# controller_2.net
KiCad netlist of a schematic drawn in EasyEDA Pro
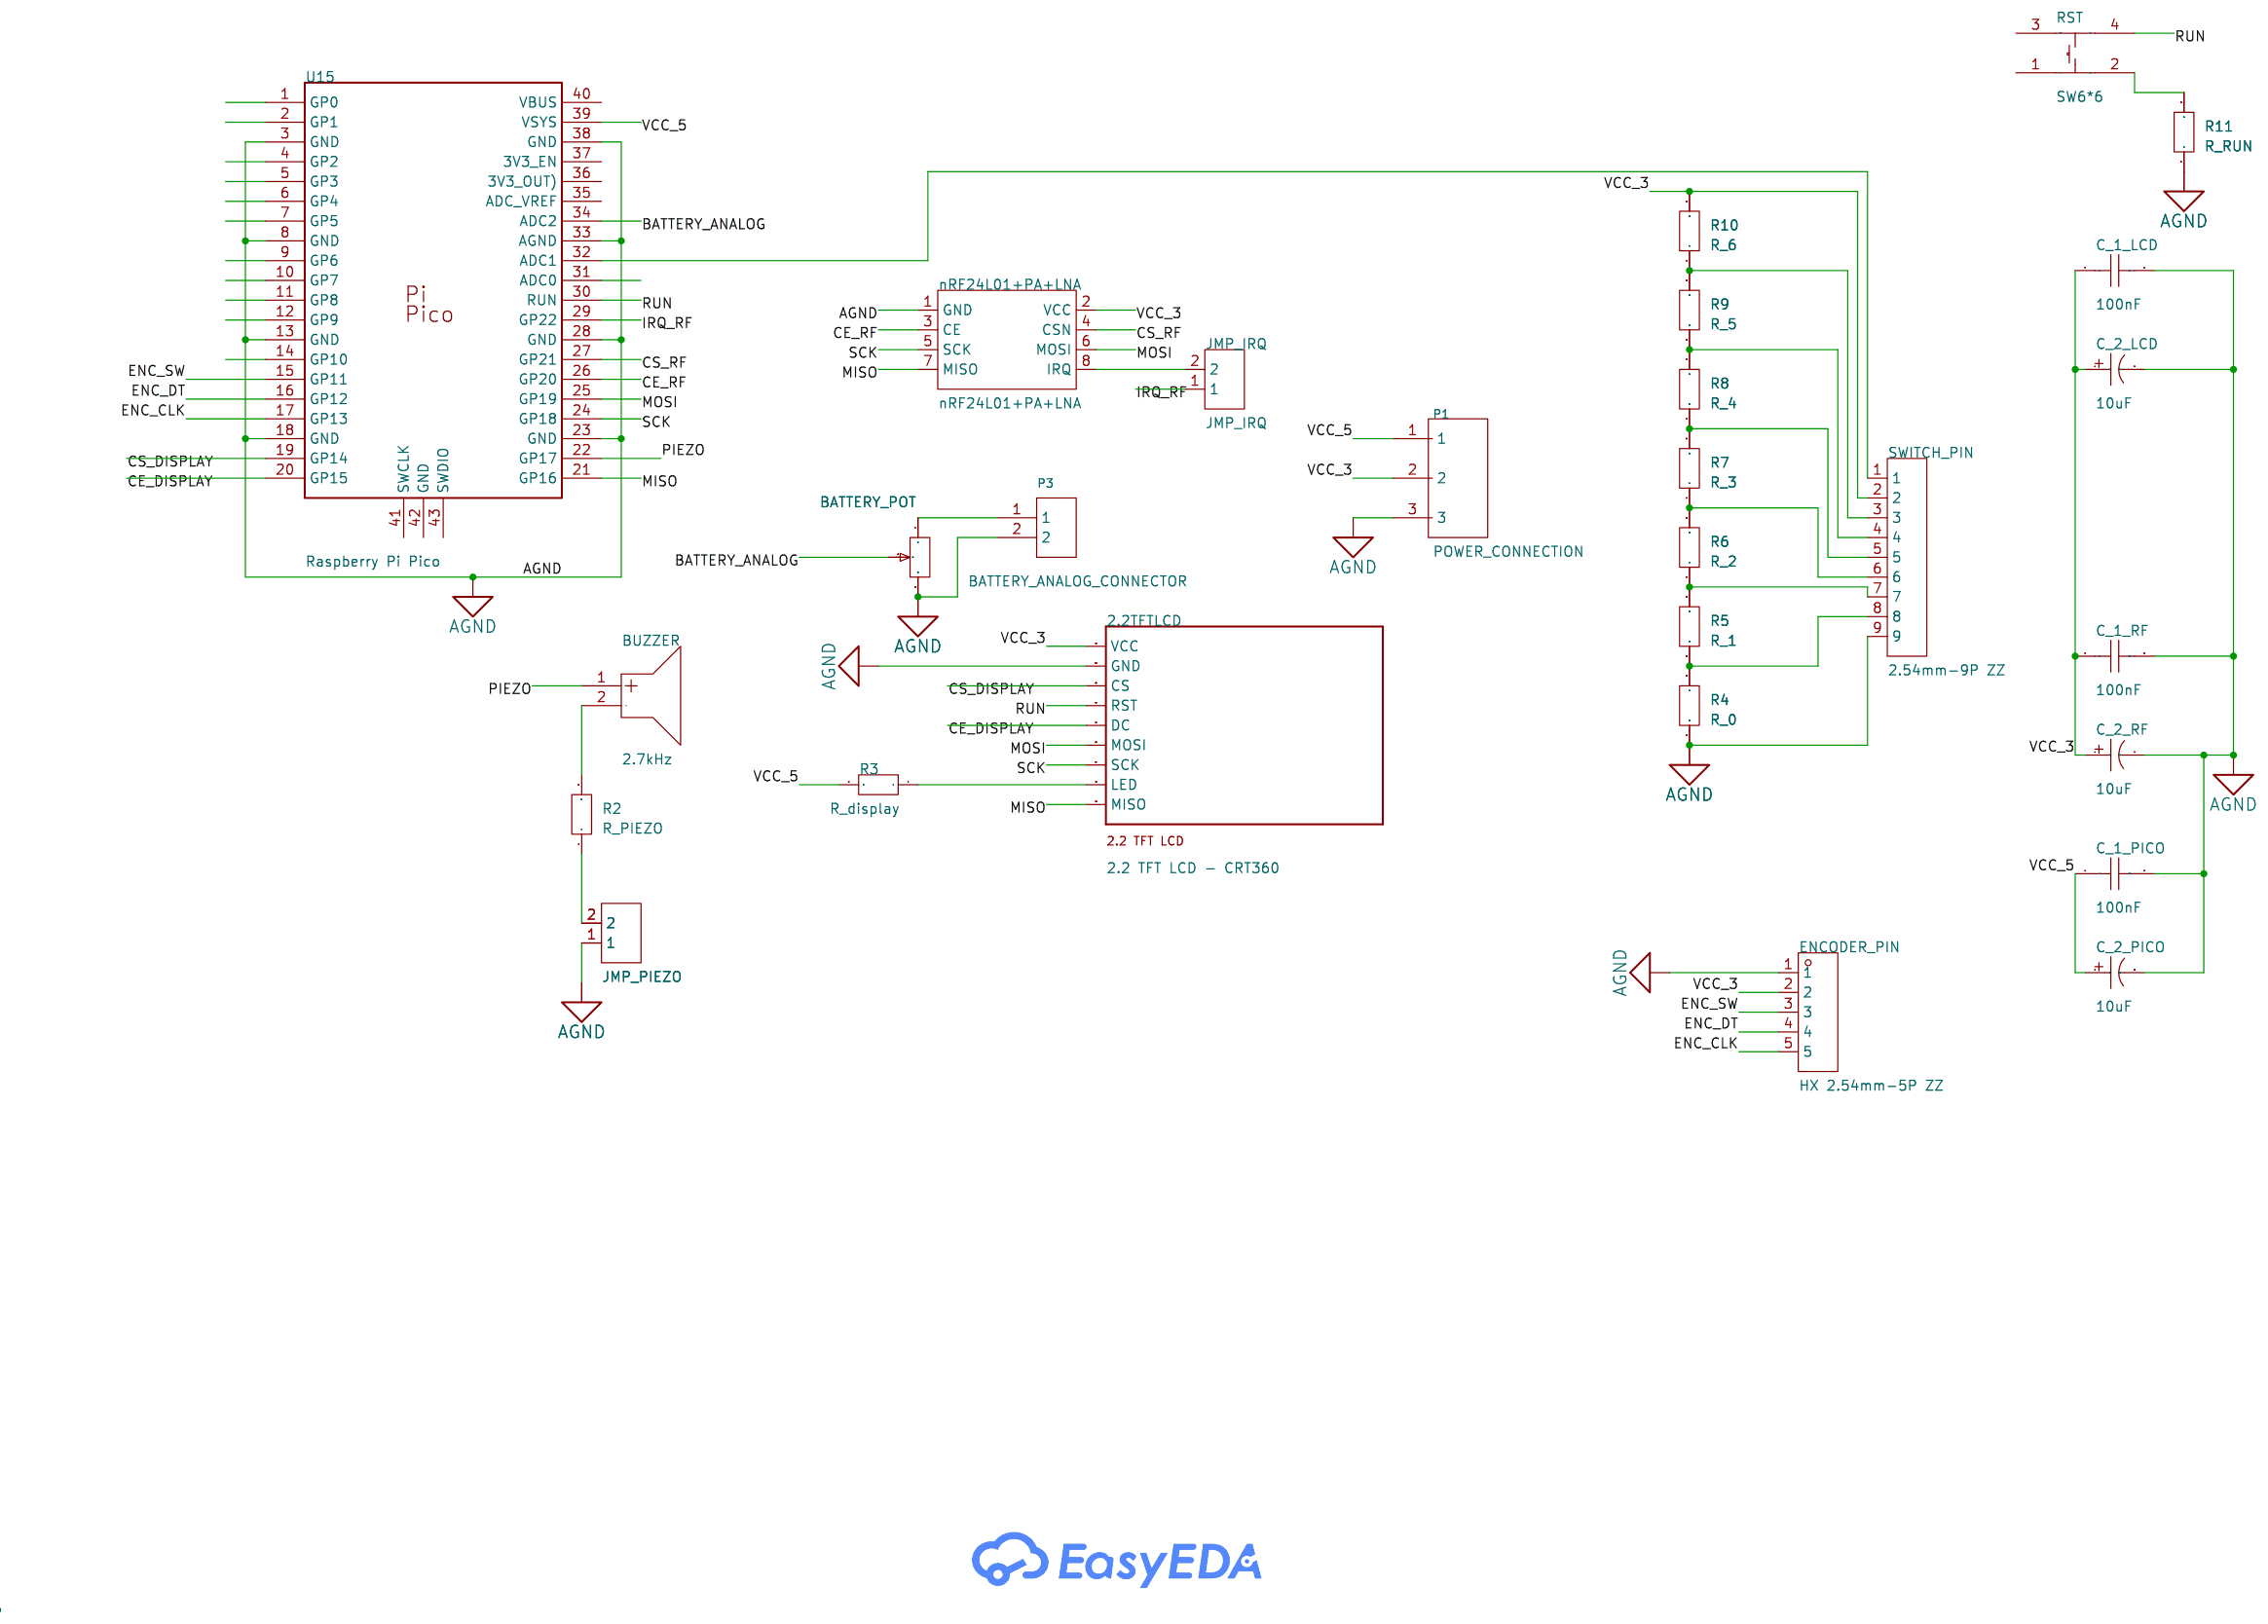
[diagram p0: schematic sheet]

(export (version "E")
  (design (tool "Eeschema 10.0.6"))
  (components
    (comp (ref "2.2TFTLCD")
      (value "2.2 TFT LCD - CRT360")
      (libsource (lib "easyedapro") (part "2.2 TFT LCD - CRT360"))
    )
    (comp (ref "BUZZER")
      (value "2.7kHz")
      (footprint "easyedapro:BUZ-TH_BD9.0-P5.00-D0.6-FD")
      (fields (field (name "Manufacturer Part") "FMB09A03-3V") (field (name "Manufacturer") "FUET(福声科技)"))
      (libsource (lib "easyedapro") (part "FMB09A03-3V_C417385"))
    )
    (comp (ref "C_1_LCD")
      (value "100nF")
      (footprint "easyedapro:CAP-TH_L5.8-W3.6-P5.0-D0.6")
      (fields (field (name "Manufacturer Part") "178MU0002") (field (name "Manufacturer") "KNSCHA(科尼盛)"))
      (libsource (lib "easyedapro") (part "178MU0002"))
    )
    (comp (ref "C_1_PICO")
      (value "100nF")
      (footprint "easyedapro:CAP-TH_L5.8-W3.6-P5.0-D0.6")
      (fields (field (name "Manufacturer Part") "178MU0002") (field (name "Manufacturer") "KNSCHA(科尼盛)"))
      (libsource (lib "easyedapro") (part "178MU0002"))
    )
    (comp (ref "C_1_RF")
      (value "100nF")
      (footprint "easyedapro:CAP-TH_L5.8-W3.6-P5.0-D0.6")
      (fields (field (name "Manufacturer Part") "178MU0002") (field (name "Manufacturer") "KNSCHA(科尼盛)"))
      (libsource (lib "easyedapro") (part "178MU0002"))
    )
    (comp (ref "C_2_LCD")
      (value "10uF")
      (footprint "easyedapro:CAP-TH_BD8.0-P3.50-D0.6-FD")
      (fields
        (field (name "Manufacturer Part") "35ZLH220MEFC8X11.5")
        (field (name "Manufacturer") "Rubycon(红宝石)")
      )
      (libsource (lib "easyedapro") (part "35ZLH220MEFC8X11.5"))
    )
    (comp (ref "C_2_PICO")
      (value "10uF")
      (footprint "easyedapro:CAP-TH_BD8.0-P3.50-D0.6-FD")
      (fields
        (field (name "Manufacturer Part") "35ZLH220MEFC8X11.5")
        (field (name "Manufacturer") "Rubycon(红宝石)")
      )
      (libsource (lib "easyedapro") (part "35ZLH220MEFC8X11.5"))
    )
    (comp (ref "C_2_RF")
      (value "10uF")
      (footprint "easyedapro:CAP-TH_BD8.0-P3.50-D0.6-FD")
      (fields
        (field (name "Manufacturer Part") "35ZLH220MEFC8X11.5")
        (field (name "Manufacturer") "Rubycon(红宝石)")
      )
      (libsource (lib "easyedapro") (part "35ZLH220MEFC8X11.5"))
    )
    (comp (ref "ENCODER_PIN")
      (value "HX 2.54mm-5P ZZ")
      (footprint "easyedapro:CONN-TH_5P-P2.50_HX-2.54MM-5P-ZZ")
      (fields (field (name "Manufacturer") "hanxia(韩下)"))
      (libsource (lib "easyedapro") (part "HX 2.54MM-5P ZZ"))
    )
    (comp (ref "H2")
      (value "JMP_PIEZO")
      (footprint "easyedapro:HDR-TH_2P-P2.54-V-M")
      (fields (field (name "Manufacturer Part") "PZ254V-11-02P") (field (name "Manufacturer") "XFCN(兴飞)"))
      (libsource (lib "easyedapro") (part "PZ254V-11-02P"))
    )
    (comp (ref "JMP_IRQ")
      (value "JMP_IRQ")
      (footprint "easyedapro:HDR-TH_2P-P2.54-V-M")
      (fields (field (name "Manufacturer Part") "PZ254V-11-02P") (field (name "Manufacturer") "XFCN(兴飞)"))
      (libsource (lib "easyedapro") (part "PZ254V-11-02P"))
    )
    (comp (ref "nRF24L01+PA+LNA")
      (value "nRF24L01+PA+LNA")
      (footprint "easyedapro:COMM-TH_L41.0-W15.5-P2.54_NRF24L01")
      (libsource (lib "easyedapro") (part "NRF24L01+PA+LNA"))
    )
    (comp (ref "P1")
      (value "POWER_CONNECTION")
      (footprint "easyedapro:CONN-TH_3P-P5.00_WJ126V-5.0-3P")
      (fields
        (field (name "Manufacturer Part") "WJ126V-5.0-3P")
        (field (name "Manufacturer") "KANGNEX(康奈克斯电气)")
      )
      (libsource (lib "easyedapro") (part "WJ126V-5.0-3P"))
    )
    (comp (ref "P3")
      (value "BATTERY_ANALOG_CONNECTOR")
      (footprint "easyedapro:CONN-TH_2P-P5.00_WJ301V-5.00-2P")
      (fields
        (field (name "Manufacturer Part") "WJ301V-5.0-2P")
        (field (name "Manufacturer") "KANGNEX(康奈克斯电气)")
      )
      (libsource (lib "easyedapro") (part "WJ301V-5.0-2P"))
    )
    (comp (ref "R1")
      (value "20kΩ")
      (footprint "easyedapro:RES-ADJ-TH_3296X")
      (fields (field (name "Manufacturer Part") "3296X-203") (field (name "Manufacturer") "BAOTER(宝特)"))
      (libsource (lib "easyedapro") (part "3296X-203"))
    )
    (comp (ref "R2")
      (value "10kΩ")
      (footprint "easyedapro:RES-TH_BD5.0-L15.5-P19.50-D0.7")
      (fields
        (field (name "Manufacturer Part") "MF02SFF1002A10")
        (field (name "Manufacturer") "UNI-ROYAL(厚声)")
      )
      (libsource (lib "easyedapro") (part "MF02SFF1002A10"))
    )
    (comp (ref "R3")
      (value "10kΩ")
      (footprint "easyedapro:RES-TH_BD5.0-L15.5-P19.50-D0.7")
      (fields
        (field (name "Manufacturer Part") "MF02SFF1002A10")
        (field (name "Manufacturer") "UNI-ROYAL(厚声)")
      )
      (libsource (lib "easyedapro") (part "MF02SFF1002A10"))
    )
    (comp (ref "R4")
      (value "10kΩ")
      (footprint "easyedapro:RES-TH_BD5.0-L15.5-P19.50-D0.7")
      (fields
        (field (name "Manufacturer Part") "MF02SFF1002A10")
        (field (name "Manufacturer") "UNI-ROYAL(厚声)")
      )
      (libsource (lib "easyedapro") (part "MF02SFF1002A10"))
    )
    (comp (ref "R5")
      (value "10kΩ")
      (footprint "easyedapro:RES-TH_BD5.0-L15.5-P19.50-D0.7")
      (fields
        (field (name "Manufacturer Part") "MF02SFF1002A10")
        (field (name "Manufacturer") "UNI-ROYAL(厚声)")
      )
      (libsource (lib "easyedapro") (part "MF02SFF1002A10"))
    )
    (comp (ref "R6")
      (value "10kΩ")
      (footprint "easyedapro:RES-TH_BD5.0-L15.5-P19.50-D0.7")
      (fields
        (field (name "Manufacturer Part") "MF02SFF1002A10")
        (field (name "Manufacturer") "UNI-ROYAL(厚声)")
      )
      (libsource (lib "easyedapro") (part "MF02SFF1002A10"))
    )
    (comp (ref "R7")
      (value "10kΩ")
      (footprint "easyedapro:RES-TH_BD5.0-L15.5-P19.50-D0.7")
      (fields
        (field (name "Manufacturer Part") "MF02SFF1002A10")
        (field (name "Manufacturer") "UNI-ROYAL(厚声)")
      )
      (libsource (lib "easyedapro") (part "MF02SFF1002A10"))
    )
    (comp (ref "R8")
      (value "10kΩ")
      (footprint "easyedapro:RES-TH_BD5.0-L15.5-P19.50-D0.7")
      (fields
        (field (name "Manufacturer Part") "MF02SFF1002A10")
        (field (name "Manufacturer") "UNI-ROYAL(厚声)")
      )
      (libsource (lib "easyedapro") (part "MF02SFF1002A10"))
    )
    (comp (ref "R9")
      (value "10kΩ")
      (footprint "easyedapro:RES-TH_BD5.0-L15.5-P19.50-D0.7")
      (fields
        (field (name "Manufacturer Part") "MF02SFF1002A10")
        (field (name "Manufacturer") "UNI-ROYAL(厚声)")
      )
      (libsource (lib "easyedapro") (part "MF02SFF1002A10"))
    )
    (comp (ref "R10")
      (value "10kΩ")
      (footprint "easyedapro:RES-TH_BD5.0-L15.5-P19.50-D0.7")
      (fields
        (field (name "Manufacturer Part") "MF02SFF1002A10")
        (field (name "Manufacturer") "UNI-ROYAL(厚声)")
      )
      (libsource (lib "easyedapro") (part "MF02SFF1002A10"))
    )
    (comp (ref "R11")
      (value "10kΩ")
      (footprint "easyedapro:RES-TH_BD5.0-L15.5-P19.50-D0.7")
      (fields
        (field (name "Manufacturer Part") "MF02SFF1002A10")
        (field (name "Manufacturer") "UNI-ROYAL(厚声)")
      )
      (libsource (lib "easyedapro") (part "MF02SFF1002A10"))
    )
    (comp (ref "RST")
      (value "SW6*6")
      (footprint "easyedapro:KEY-TH_4P-L6.0-W6.0-P4.5-LS6.5-TL")
      (libsource (lib "easyedapro") (part "SW6*6"))
    )
    (comp (ref "SWITCH_PIN")
      (value "2.54mm-9P ZZ")
      (footprint "easyedapro:CONN-TH_9P-P2.50_HX-2.54MM-9P-ZZ")
      (fields (field (name "Manufacturer") "SHOU HAN(首韩)"))
      (libsource (lib "easyedapro") (part "2.54MM-9P ZZ"))
    )
    (comp (ref "U15")
      (value "Raspberry Pi Pico")
      (fields (field (name "Manufacturer Part") "Pi Pico") (field (name "Manufacturer") "Raspberry Pi"))
      (libsource (lib "easyedapro") (part "Raspberry Pi Pico"))
    )
  )
  (nets
    (net (code "1") (name "/BATTERY_ANALOG") (class "Default")
      (node (ref "R1") (pin "2") (pinfunction "2_2") (pintype "input"))
      (node (ref "U15") (pin "34") (pinfunction "ADC2_34") (pintype "unspecified"))
    )
    (net (code "2") (name "/CE_DISPLAY") (class "Default")
      (node (ref "2.2TFTLCD") (pin "DC") (pinfunction "DC_DC") (pintype "unspecified"))
      (node (ref "U15") (pin "20") (pinfunction "GP15_20") (pintype "unspecified"))
    )
    (net (code "3") (name "/CE_RF") (class "Default")
      (node (ref "U15") (pin "26") (pinfunction "GP20_26") (pintype "unspecified"))
      (node (ref "nRF24L01+PA+LNA") (pin "3") (pinfunction "CE_3") (pintype "unspecified"))
    )
    (net (code "4") (name "/CS_DISPLAY") (class "Default")
      (node (ref "2.2TFTLCD") (pin "CS") (pinfunction "CS_CS") (pintype "unspecified"))
      (node (ref "U15") (pin "19") (pinfunction "GP14_19") (pintype "unspecified"))
    )
    (net (code "5") (name "/CS_RF") (class "Default")
      (node (ref "U15") (pin "27") (pinfunction "GP21_27") (pintype "unspecified"))
      (node (ref "nRF24L01+PA+LNA") (pin "4") (pinfunction "CSN_4") (pintype "unspecified"))
    )
    (net (code "6") (name "/ENC_CLK") (class "Default")
      (node (ref "ENCODER_PIN") (pin "5") (pinfunction "5_5") (pintype "unspecified"))
      (node (ref "U15") (pin "17") (pinfunction "GP13_17") (pintype "unspecified"))
    )
    (net (code "7") (name "/ENC_DT") (class "Default")
      (node (ref "ENCODER_PIN") (pin "4") (pinfunction "4_4") (pintype "unspecified"))
      (node (ref "U15") (pin "16") (pinfunction "GP12_16") (pintype "unspecified"))
    )
    (net (code "8") (name "/ENC_SW") (class "Default")
      (node (ref "ENCODER_PIN") (pin "3") (pinfunction "3_3") (pintype "unspecified"))
      (node (ref "U15") (pin "15") (pinfunction "GP11_15") (pintype "unspecified"))
    )
    (net (code "9") (name "/IRQ_RF") (class "Default")
      (node (ref "JMP_IRQ") (pin "1") (pinfunction "1_1") (pintype "unspecified"))
      (node (ref "U15") (pin "29") (pinfunction "GP22_29") (pintype "unspecified"))
    )
    (net (code "10") (name "/MISO") (class "Default")
      (node (ref "2.2TFTLCD") (pin "MISO") (pinfunction "MISO_MISO") (pintype "unspecified"))
      (node (ref "U15") (pin "21") (pinfunction "GP16_21") (pintype "unspecified"))
      (node (ref "nRF24L01+PA+LNA") (pin "7") (pinfunction "MISO_7") (pintype "unspecified"))
    )
    (net (code "11") (name "/MOSI") (class "Default")
      (node (ref "2.2TFTLCD") (pin "MOSI") (pinfunction "MOSI_MOSI") (pintype "unspecified"))
      (node (ref "U15") (pin "25") (pinfunction "GP19_25") (pintype "unspecified"))
      (node (ref "nRF24L01+PA+LNA") (pin "6") (pinfunction "MOSI_6") (pintype "unspecified"))
    )
    (net (code "12") (name "/PIEZO") (class "Default")
      (node (ref "BUZZER") (pin "1") (pinfunction "+_1") (pintype "unspecified"))
      (node (ref "U15") (pin "22") (pinfunction "GP17_22") (pintype "unspecified"))
    )
    (net (code "13") (name "/RUN") (class "Default")
      (node (ref "2.2TFTLCD") (pin "RST") (pinfunction "RST_RST") (pintype "unspecified"))
      (node (ref "RST") (pin "4") (pinfunction "4_4") (pintype "unspecified"))
      (node (ref "U15") (pin "30") (pinfunction "RUN_30") (pintype "unspecified"))
    )
    (net (code "14") (name "/SCK") (class "Default")
      (node (ref "2.2TFTLCD") (pin "SCK") (pinfunction "SCK_SCK") (pintype "unspecified"))
      (node (ref "U15") (pin "24") (pinfunction "GP18_24") (pintype "unspecified"))
      (node (ref "nRF24L01+PA+LNA") (pin "5") (pinfunction "SCK_5") (pintype "unspecified"))
    )
    (net (code "15") (name "/VCC_3") (class "Default")
      (node (ref "2.2TFTLCD") (pin "VCC") (pinfunction "VCC_VCC") (pintype "unspecified"))
      (node (ref "C_1_LCD") (pin "1") (pinfunction "1_1") (pintype "unspecified"))
      (node (ref "C_1_RF") (pin "1") (pinfunction "1_1") (pintype "unspecified"))
      (node (ref "C_2_LCD") (pin "1") (pinfunction "1_1") (pintype "input"))
      (node (ref "C_2_RF") (pin "1") (pinfunction "1_1") (pintype "input"))
      (node (ref "ENCODER_PIN") (pin "2") (pinfunction "2_2") (pintype "unspecified"))
      (node (ref "P1") (pin "2") (pinfunction "2_2") (pintype "input"))
      (node (ref "R10") (pin "2") (pinfunction "2_2") (pintype "unspecified"))
      (node (ref "SWITCH_PIN") (pin "2") (pinfunction "2_2") (pintype "unspecified"))
      (node (ref "nRF24L01+PA+LNA") (pin "2") (pinfunction "VCC_2") (pintype "unspecified"))
    )
    (net (code "16") (name "/VCC_5") (class "Default")
      (node (ref "C_1_PICO") (pin "1") (pinfunction "1_1") (pintype "unspecified"))
      (node (ref "C_2_PICO") (pin "1") (pinfunction "1_1") (pintype "input"))
      (node (ref "P1") (pin "1") (pinfunction "1_1") (pintype "input"))
      (node (ref "R3") (pin "2") (pinfunction "2_2") (pintype "unspecified"))
      (node (ref "U15") (pin "39") (pinfunction "VSYS_39") (pintype "unspecified"))
    )
    (net (code "17") (name "AGND") (class "Default")
      (node (ref "2.2TFTLCD") (pin "GND") (pinfunction "GND_GND") (pintype "unspecified"))
      (node (ref "C_1_LCD") (pin "2") (pinfunction "2_2") (pintype "unspecified"))
      (node (ref "C_1_PICO") (pin "2") (pinfunction "2_2") (pintype "unspecified"))
      (node (ref "C_1_RF") (pin "2") (pinfunction "2_2") (pintype "unspecified"))
      (node (ref "C_2_LCD") (pin "2") (pinfunction "2_2") (pintype "input"))
      (node (ref "C_2_PICO") (pin "2") (pinfunction "2_2") (pintype "input"))
      (node (ref "C_2_RF") (pin "2") (pinfunction "2_2") (pintype "input"))
      (node (ref "ENCODER_PIN") (pin "1") (pinfunction "1_1") (pintype "unspecified"))
      (node (ref "H2") (pin "1") (pinfunction "1_1") (pintype "unspecified"))
      (node (ref "P1") (pin "3") (pinfunction "3_3") (pintype "input"))
      (node (ref "P3") (pin "2") (pinfunction "2_2") (pintype "input"))
      (node (ref "R1") (pin "3") (pinfunction "3_3") (pintype "input"))
      (node (ref "R11") (pin "1") (pinfunction "1_1") (pintype "unspecified"))
      (node (ref "R4") (pin "1") (pinfunction "1_1") (pintype "unspecified"))
      (node (ref "SWITCH_PIN") (pin "9") (pinfunction "9_9") (pintype "unspecified"))
      (node (ref "U15") (pin "13") (pinfunction "GND_13") (pintype "unspecified"))
      (node (ref "U15") (pin "18") (pinfunction "GND_18") (pintype "unspecified"))
      (node (ref "U15") (pin "23") (pinfunction "GND_23") (pintype "unspecified"))
      (node (ref "U15") (pin "28") (pinfunction "GND_28") (pintype "unspecified"))
      (node (ref "U15") (pin "3") (pinfunction "GND_3") (pintype "unspecified"))
      (node (ref "U15") (pin "33") (pinfunction "AGND_33") (pintype "unspecified"))
      (node (ref "U15") (pin "38") (pinfunction "GND_38") (pintype "unspecified"))
      (node (ref "U15") (pin "8") (pinfunction "GND_8") (pintype "unspecified"))
      (node (ref "nRF24L01+PA+LNA") (pin "1") (pinfunction "GND_1") (pintype "unspecified"))
    )
    (net (code "18") (name "Net-(2.2TFTLCD-PadLED)") (class "Default")
      (node (ref "2.2TFTLCD") (pin "LED") (pinfunction "LED_LED") (pintype "unspecified"))
      (node (ref "R3") (pin "1") (pinfunction "1_1") (pintype "unspecified"))
    )
    (net (code "19") (name "Net-(BUZZER--)") (class "Default")
      (node (ref "BUZZER") (pin "2") (pinfunction "-_2") (pintype "unspecified"))
      (node (ref "R2") (pin "2") (pinfunction "2_2") (pintype "unspecified"))
    )
    (net (code "20") (name "Net-(H2-Pad2)") (class "Default")
      (node (ref "H2") (pin "2") (pinfunction "2_2") (pintype "unspecified"))
      (node (ref "R2") (pin "1") (pinfunction "1_1") (pintype "unspecified"))
    )
    (net (code "21") (name "Net-(P3-Pad1)") (class "Default")
      (node (ref "P3") (pin "1") (pinfunction "1_1") (pintype "input"))
      (node (ref "R1") (pin "1") (pinfunction "1_1") (pintype "input"))
    )
    (net (code "22") (name "Net-(R4-Pad2)") (class "Default")
      (node (ref "R4") (pin "2") (pinfunction "2_2") (pintype "unspecified"))
      (node (ref "R5") (pin "1") (pinfunction "1_1") (pintype "unspecified"))
      (node (ref "SWITCH_PIN") (pin "8") (pinfunction "8_8") (pintype "unspecified"))
    )
    (net (code "23") (name "Net-(R5-Pad2)") (class "Default")
      (node (ref "R5") (pin "2") (pinfunction "2_2") (pintype "unspecified"))
      (node (ref "R6") (pin "1") (pinfunction "1_1") (pintype "unspecified"))
      (node (ref "SWITCH_PIN") (pin "7") (pinfunction "7_7") (pintype "unspecified"))
    )
    (net (code "24") (name "Net-(R6-Pad2)") (class "Default")
      (node (ref "R6") (pin "2") (pinfunction "2_2") (pintype "unspecified"))
      (node (ref "R7") (pin "1") (pinfunction "1_1") (pintype "unspecified"))
      (node (ref "SWITCH_PIN") (pin "6") (pinfunction "6_6") (pintype "unspecified"))
    )
    (net (code "25") (name "Net-(R7-Pad2)") (class "Default")
      (node (ref "R7") (pin "2") (pinfunction "2_2") (pintype "unspecified"))
      (node (ref "R8") (pin "1") (pinfunction "1_1") (pintype "unspecified"))
      (node (ref "SWITCH_PIN") (pin "5") (pinfunction "5_5") (pintype "unspecified"))
    )
    (net (code "26") (name "Net-(R8-Pad2)") (class "Default")
      (node (ref "R8") (pin "2") (pinfunction "2_2") (pintype "unspecified"))
      (node (ref "R9") (pin "1") (pinfunction "1_1") (pintype "unspecified"))
      (node (ref "SWITCH_PIN") (pin "4") (pinfunction "4_4") (pintype "unspecified"))
    )
    (net (code "27") (name "Net-(R10-Pad1)") (class "Default")
      (node (ref "R10") (pin "1") (pinfunction "1_1") (pintype "unspecified"))
      (node (ref "R9") (pin "2") (pinfunction "2_2") (pintype "unspecified"))
      (node (ref "SWITCH_PIN") (pin "3") (pinfunction "3_3") (pintype "unspecified"))
    )
    (net (code "28") (name "Net-(R11-Pad2)") (class "Default")
      (node (ref "R11") (pin "2") (pinfunction "2_2") (pintype "unspecified"))
      (node (ref "RST") (pin "2") (pinfunction "2_2") (pintype "unspecified"))
    )
    (net (code "29") (name "Net-(U15-ADC1)") (class "Default")
      (node (ref "SWITCH_PIN") (pin "1") (pinfunction "1_1") (pintype "unspecified"))
      (node (ref "U15") (pin "32") (pinfunction "ADC1_32") (pintype "unspecified"))
    )
    (net (code "30") (name "Net-(nRF24L01+PA+LNA-IRQ)") (class "Default")
      (node (ref "JMP_IRQ") (pin "2") (pinfunction "2_2") (pintype "unspecified"))
      (node (ref "nRF24L01+PA+LNA") (pin "8") (pinfunction "IRQ_8") (pintype "unspecified"))
    )
    (net (code "31") (name "unconnected-(RST-Pad1)") (class "Default")
      (node (ref "RST") (pin "1") (pinfunction "1_1") (pintype "unspecified"))
    )
    (net (code "32") (name "unconnected-(RST-Pad3)") (class "Default")
      (node (ref "RST") (pin "3") (pinfunction "3_3") (pintype "unspecified"))
    )
    (net (code "33") (name "unconnected-(U15-3V3_EN-Pad37)") (class "Default")
      (node (ref "U15") (pin "37") (pinfunction "3V3_EN_37") (pintype "unspecified"))
    )
    (net (code "34") (name "unconnected-(U15-3V3_OUT)-Pad36)") (class "Default")
      (node (ref "U15") (pin "36") (pinfunction "3V3_OUT)_36") (pintype "unspecified"))
    )
    (net (code "35") (name "unconnected-(U15-ADC0-Pad31)") (class "Default")
      (node (ref "U15") (pin "31") (pinfunction "ADC0_31") (pintype "unspecified"))
    )
    (net (code "36") (name "unconnected-(U15-ADC_VREF-Pad35)") (class "Default")
      (node (ref "U15") (pin "35") (pinfunction "ADC_VREF_35") (pintype "unspecified"))
    )
    (net (code "37") (name "unconnected-(U15-GND-Pad42)") (class "Default")
      (node (ref "U15") (pin "42") (pinfunction "GND_42") (pintype "unspecified"))
    )
    (net (code "38") (name "unconnected-(U15-GP0-Pad1)") (class "Default")
      (node (ref "U15") (pin "1") (pinfunction "GP0_1") (pintype "unspecified"))
    )
    (net (code "39") (name "unconnected-(U15-GP1-Pad2)") (class "Default")
      (node (ref "U15") (pin "2") (pinfunction "GP1_2") (pintype "unspecified"))
    )
    (net (code "40") (name "unconnected-(U15-GP2-Pad4)") (class "Default")
      (node (ref "U15") (pin "4") (pinfunction "GP2_4") (pintype "unspecified"))
    )
    (net (code "41") (name "unconnected-(U15-GP3-Pad5)") (class "Default")
      (node (ref "U15") (pin "5") (pinfunction "GP3_5") (pintype "unspecified"))
    )
    (net (code "42") (name "unconnected-(U15-GP4-Pad6)") (class "Default")
      (node (ref "U15") (pin "6") (pinfunction "GP4_6") (pintype "unspecified"))
    )
    (net (code "43") (name "unconnected-(U15-GP5-Pad7)") (class "Default")
      (node (ref "U15") (pin "7") (pinfunction "GP5_7") (pintype "unspecified"))
    )
    (net (code "44") (name "unconnected-(U15-GP6-Pad9)") (class "Default")
      (node (ref "U15") (pin "9") (pinfunction "GP6_9") (pintype "unspecified"))
    )
    (net (code "45") (name "unconnected-(U15-GP7-Pad10)") (class "Default")
      (node (ref "U15") (pin "10") (pinfunction "GP7_10") (pintype "unspecified"))
    )
    (net (code "46") (name "unconnected-(U15-GP8-Pad11)") (class "Default")
      (node (ref "U15") (pin "11") (pinfunction "GP8_11") (pintype "unspecified"))
    )
    (net (code "47") (name "unconnected-(U15-GP9-Pad12)") (class "Default")
      (node (ref "U15") (pin "12") (pinfunction "GP9_12") (pintype "unspecified"))
    )
    (net (code "48") (name "unconnected-(U15-GP10-Pad14)") (class "Default")
      (node (ref "U15") (pin "14") (pinfunction "GP10_14") (pintype "unspecified"))
    )
    (net (code "49") (name "unconnected-(U15-SWCLK-Pad41)") (class "Default")
      (node (ref "U15") (pin "41") (pinfunction "SWCLK_41") (pintype "unspecified"))
    )
    (net (code "50") (name "unconnected-(U15-SWDIO-Pad43)") (class "Default")
      (node (ref "U15") (pin "43") (pinfunction "SWDIO_43") (pintype "unspecified"))
    )
    (net (code "51") (name "unconnected-(U15-VBUS-Pad40)") (class "Default")
      (node (ref "U15") (pin "40") (pinfunction "VBUS_40") (pintype "unspecified"))
    )
  )
)
